# D_Input.net
KiCad netlist of a schematic drawn in Altium Designer
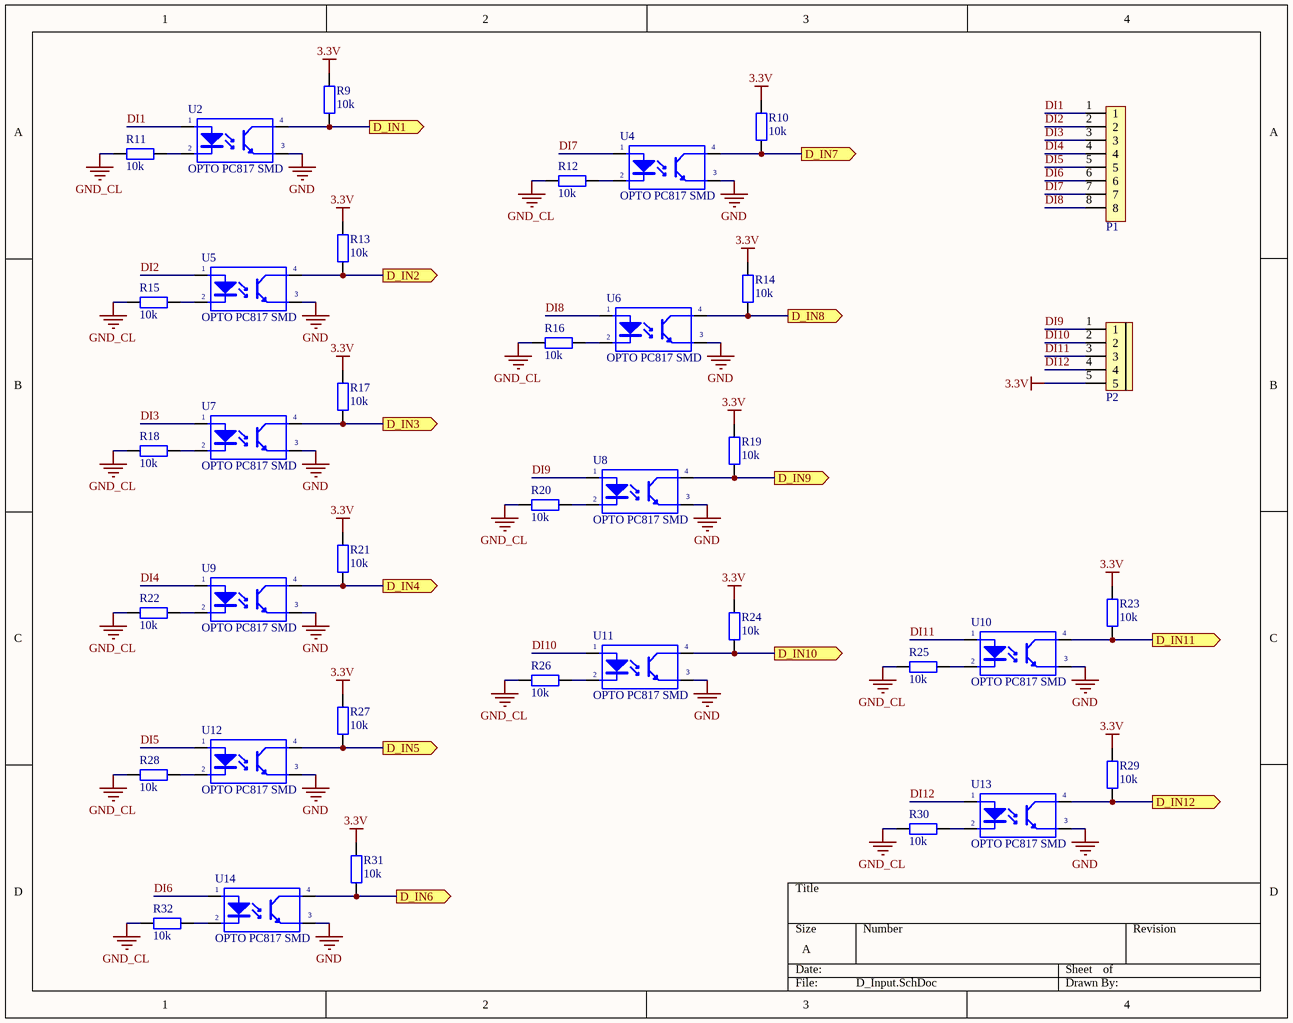
[diagram p0: D_Input.SchDoc]

(export (version "E")
  (design (tool "Eeschema 10.0.6"))
  (components
    (comp (ref "P1")
      (value "CON 8 EDG5.08")
      (footprint "CON 8 8EDG5.08")
      (description "Cắm")
      (libsource (lib "Altium_Lib_by_KhueNguyenCreator") (part "CON 8 EDG5.08"))
    )
    (comp (ref "P2")
      (value "CON 5 EDG5.08")
      (footprint "CON 5 5EDG5.08")
      (description "Cắm")
      (libsource (lib "Altium_Lib_by_KhueNguyenCreator") (part "CON 5 EDG5.08"))
    )
    (comp (ref "R9")
      (value "10k")
      (footprint "tro smd 0805")
      (description "Dán")
      (libsource (lib "Altium_Lib_by_KhueNguyenCreator") (part "Tro 0805 1% 10k"))
    )
    (comp (ref "R10")
      (value "10k")
      (footprint "tro smd 0805")
      (description "Dán")
      (libsource (lib "Altium_Lib_by_KhueNguyenCreator") (part "Tro 0805 1% 10k"))
    )
    (comp (ref "R11")
      (value "10k")
      (footprint "tro smd 0805")
      (description "Dán")
      (libsource (lib "Altium_Lib_by_KhueNguyenCreator") (part "Tro 0805 1% 10k"))
    )
    (comp (ref "R12")
      (value "10k")
      (footprint "tro smd 0805")
      (description "Dán")
      (libsource (lib "Altium_Lib_by_KhueNguyenCreator") (part "Tro 0805 1% 10k"))
    )
    (comp (ref "R13")
      (value "10k")
      (footprint "tro smd 0805")
      (description "Dán")
      (libsource (lib "Altium_Lib_by_KhueNguyenCreator") (part "Tro 0805 1% 10k"))
    )
    (comp (ref "R14")
      (value "10k")
      (footprint "tro smd 0805")
      (description "Dán")
      (libsource (lib "Altium_Lib_by_KhueNguyenCreator") (part "Tro 0805 1% 10k"))
    )
    (comp (ref "R15")
      (value "10k")
      (footprint "tro smd 0805")
      (description "Dán")
      (libsource (lib "Altium_Lib_by_KhueNguyenCreator") (part "Tro 0805 1% 10k"))
    )
    (comp (ref "R16")
      (value "10k")
      (footprint "tro smd 0805")
      (description "Dán")
      (libsource (lib "Altium_Lib_by_KhueNguyenCreator") (part "Tro 0805 1% 10k"))
    )
    (comp (ref "R17")
      (value "10k")
      (footprint "tro smd 0805")
      (description "Dán")
      (libsource (lib "Altium_Lib_by_KhueNguyenCreator") (part "Tro 0805 1% 10k"))
    )
    (comp (ref "R18")
      (value "10k")
      (footprint "tro smd 0805")
      (description "Dán")
      (libsource (lib "Altium_Lib_by_KhueNguyenCreator") (part "Tro 0805 1% 10k"))
    )
    (comp (ref "R19")
      (value "10k")
      (footprint "tro smd 0805")
      (description "Dán")
      (libsource (lib "Altium_Lib_by_KhueNguyenCreator") (part "Tro 0805 1% 10k"))
    )
    (comp (ref "R20")
      (value "10k")
      (footprint "tro smd 0805")
      (description "Dán")
      (libsource (lib "Altium_Lib_by_KhueNguyenCreator") (part "Tro 0805 1% 10k"))
    )
    (comp (ref "R21")
      (value "10k")
      (footprint "tro smd 0805")
      (description "Dán")
      (libsource (lib "Altium_Lib_by_KhueNguyenCreator") (part "Tro 0805 1% 10k"))
    )
    (comp (ref "R22")
      (value "10k")
      (footprint "tro smd 0805")
      (description "Dán")
      (libsource (lib "Altium_Lib_by_KhueNguyenCreator") (part "Tro 0805 1% 10k"))
    )
    (comp (ref "R23")
      (value "10k")
      (footprint "tro smd 0805")
      (description "Dán")
      (libsource (lib "Altium_Lib_by_KhueNguyenCreator") (part "Tro 0805 1% 10k"))
    )
    (comp (ref "R24")
      (value "10k")
      (footprint "tro smd 0805")
      (description "Dán")
      (libsource (lib "Altium_Lib_by_KhueNguyenCreator") (part "Tro 0805 1% 10k"))
    )
    (comp (ref "R25")
      (value "10k")
      (footprint "tro smd 0805")
      (description "Dán")
      (libsource (lib "Altium_Lib_by_KhueNguyenCreator") (part "Tro 0805 1% 10k"))
    )
    (comp (ref "R26")
      (value "10k")
      (footprint "tro smd 0805")
      (description "Dán")
      (libsource (lib "Altium_Lib_by_KhueNguyenCreator") (part "Tro 0805 1% 10k"))
    )
    (comp (ref "R27")
      (value "10k")
      (footprint "tro smd 0805")
      (description "Dán")
      (libsource (lib "Altium_Lib_by_KhueNguyenCreator") (part "Tro 0805 1% 10k"))
    )
    (comp (ref "R28")
      (value "10k")
      (footprint "tro smd 0805")
      (description "Dán")
      (libsource (lib "Altium_Lib_by_KhueNguyenCreator") (part "Tro 0805 1% 10k"))
    )
    (comp (ref "R29")
      (value "10k")
      (footprint "tro smd 0805")
      (description "Dán")
      (libsource (lib "Altium_Lib_by_KhueNguyenCreator") (part "Tro 0805 1% 10k"))
    )
    (comp (ref "R30")
      (value "10k")
      (footprint "tro smd 0805")
      (description "Dán")
      (libsource (lib "Altium_Lib_by_KhueNguyenCreator") (part "Tro 0805 1% 10k"))
    )
    (comp (ref "R31")
      (value "10k")
      (footprint "tro smd 0805")
      (description "Dán")
      (libsource (lib "Altium_Lib_by_KhueNguyenCreator") (part "Tro 0805 1% 10k"))
    )
    (comp (ref "R32")
      (value "10k")
      (footprint "tro smd 0805")
      (description "Dán")
      (libsource (lib "Altium_Lib_by_KhueNguyenCreator") (part "Tro 0805 1% 10k"))
    )
    (comp (ref "U2")
      (value "OPTO PC817 SMD")
      (footprint "SOP4")
      (description "Single Opto")
      (libsource (lib "Altium_Lib_by_KhueNguyenCreator") (part "OPTO PC817 SMD"))
    )
    (comp (ref "U4")
      (value "OPTO PC817 SMD")
      (footprint "SOP4")
      (description "Single Opto")
      (libsource (lib "Altium_Lib_by_KhueNguyenCreator") (part "OPTO PC817 SMD"))
    )
    (comp (ref "U5")
      (value "OPTO PC817 SMD")
      (footprint "SOP4")
      (description "Single Opto")
      (libsource (lib "Altium_Lib_by_KhueNguyenCreator") (part "OPTO PC817 SMD"))
    )
    (comp (ref "U6")
      (value "OPTO PC817 SMD")
      (footprint "SOP4")
      (description "Single Opto")
      (libsource (lib "Altium_Lib_by_KhueNguyenCreator") (part "OPTO PC817 SMD"))
    )
    (comp (ref "U7")
      (value "OPTO PC817 SMD")
      (footprint "SOP4")
      (description "Single Opto")
      (libsource (lib "Altium_Lib_by_KhueNguyenCreator") (part "OPTO PC817 SMD"))
    )
    (comp (ref "U8")
      (value "OPTO PC817 SMD")
      (footprint "SOP4")
      (description "Single Opto")
      (libsource (lib "Altium_Lib_by_KhueNguyenCreator") (part "OPTO PC817 SMD"))
    )
    (comp (ref "U9")
      (value "OPTO PC817 SMD")
      (footprint "SOP4")
      (description "Single Opto")
      (libsource (lib "Altium_Lib_by_KhueNguyenCreator") (part "OPTO PC817 SMD"))
    )
    (comp (ref "U10")
      (value "OPTO PC817 SMD")
      (footprint "SOP4")
      (description "Single Opto")
      (libsource (lib "Altium_Lib_by_KhueNguyenCreator") (part "OPTO PC817 SMD"))
    )
    (comp (ref "U11")
      (value "OPTO PC817 SMD")
      (footprint "SOP4")
      (description "Single Opto")
      (libsource (lib "Altium_Lib_by_KhueNguyenCreator") (part "OPTO PC817 SMD"))
    )
    (comp (ref "U12")
      (value "OPTO PC817 SMD")
      (footprint "SOP4")
      (description "Single Opto")
      (libsource (lib "Altium_Lib_by_KhueNguyenCreator") (part "OPTO PC817 SMD"))
    )
    (comp (ref "U13")
      (value "OPTO PC817 SMD")
      (footprint "SOP4")
      (description "Single Opto")
      (libsource (lib "Altium_Lib_by_KhueNguyenCreator") (part "OPTO PC817 SMD"))
    )
    (comp (ref "U14")
      (value "OPTO PC817 SMD")
      (footprint "SOP4")
      (description "Single Opto")
      (libsource (lib "Altium_Lib_by_KhueNguyenCreator") (part "OPTO PC817 SMD"))
    )
  )
  (nets
    (net (code "1") (name "/DI1") (class "Default")
      (node (ref "P1") (pin "1") (pinfunction "1_1") (pintype "passive"))
      (node (ref "U2") (pin "1") (pinfunction "A_1") (pintype "passive"))
    )
    (net (code "2") (name "/DI2") (class "Default")
      (node (ref "P1") (pin "2") (pinfunction "2_2") (pintype "passive"))
      (node (ref "U5") (pin "1") (pinfunction "A_1") (pintype "passive"))
    )
    (net (code "3") (name "/DI3") (class "Default")
      (node (ref "P1") (pin "3") (pinfunction "3_3") (pintype "passive"))
      (node (ref "U7") (pin "1") (pinfunction "A_1") (pintype "passive"))
    )
    (net (code "4") (name "/DI4") (class "Default")
      (node (ref "P1") (pin "4") (pinfunction "4_4") (pintype "passive"))
      (node (ref "U9") (pin "1") (pinfunction "A_1") (pintype "passive"))
    )
    (net (code "5") (name "/DI5") (class "Default")
      (node (ref "P1") (pin "5") (pinfunction "5_5") (pintype "passive"))
      (node (ref "U12") (pin "1") (pinfunction "A_1") (pintype "passive"))
    )
    (net (code "6") (name "/DI6") (class "Default")
      (node (ref "P1") (pin "6") (pinfunction "6_6") (pintype "passive"))
      (node (ref "U14") (pin "1") (pinfunction "A_1") (pintype "passive"))
    )
    (net (code "7") (name "/DI7") (class "Default")
      (node (ref "P1") (pin "7") (pinfunction "7_7") (pintype "passive"))
      (node (ref "U4") (pin "1") (pinfunction "A_1") (pintype "passive"))
    )
    (net (code "8") (name "/DI8") (class "Default")
      (node (ref "P1") (pin "8") (pinfunction "8_8") (pintype "passive"))
      (node (ref "U6") (pin "1") (pinfunction "A_1") (pintype "passive"))
    )
    (net (code "9") (name "/DI9") (class "Default")
      (node (ref "P2") (pin "1") (pinfunction "1_1") (pintype "passive"))
      (node (ref "U8") (pin "1") (pinfunction "A_1") (pintype "passive"))
    )
    (net (code "10") (name "/DI10") (class "Default")
      (node (ref "P2") (pin "2") (pinfunction "2_2") (pintype "passive"))
      (node (ref "U11") (pin "1") (pinfunction "A_1") (pintype "passive"))
    )
    (net (code "11") (name "/DI11") (class "Default")
      (node (ref "P2") (pin "3") (pinfunction "3_3") (pintype "passive"))
      (node (ref "U10") (pin "1") (pinfunction "A_1") (pintype "passive"))
    )
    (net (code "12") (name "/DI12") (class "Default")
      (node (ref "P2") (pin "4") (pinfunction "4_4") (pintype "passive"))
      (node (ref "U13") (pin "1") (pinfunction "A_1") (pintype "passive"))
    )
    (net (code "13") (name "/D_IN1") (class "Default")
      (node (ref "R9") (pin "1") (pinfunction "1_1") (pintype "passive"))
      (node (ref "U2") (pin "4") (pinfunction "C_4") (pintype "passive"))
    )
    (net (code "14") (name "/D_IN2") (class "Default")
      (node (ref "R13") (pin "1") (pinfunction "1_1") (pintype "passive"))
      (node (ref "U5") (pin "4") (pinfunction "C_4") (pintype "passive"))
    )
    (net (code "15") (name "/D_IN3") (class "Default")
      (node (ref "R17") (pin "1") (pinfunction "1_1") (pintype "passive"))
      (node (ref "U7") (pin "4") (pinfunction "C_4") (pintype "passive"))
    )
    (net (code "16") (name "/D_IN4") (class "Default")
      (node (ref "R21") (pin "1") (pinfunction "1_1") (pintype "passive"))
      (node (ref "U9") (pin "4") (pinfunction "C_4") (pintype "passive"))
    )
    (net (code "17") (name "/D_IN5") (class "Default")
      (node (ref "R27") (pin "1") (pinfunction "1_1") (pintype "passive"))
      (node (ref "U12") (pin "4") (pinfunction "C_4") (pintype "passive"))
    )
    (net (code "18") (name "/D_IN6") (class "Default")
      (node (ref "R31") (pin "1") (pinfunction "1_1") (pintype "passive"))
      (node (ref "U14") (pin "4") (pinfunction "C_4") (pintype "passive"))
    )
    (net (code "19") (name "/D_IN7") (class "Default")
      (node (ref "R10") (pin "1") (pinfunction "1_1") (pintype "passive"))
      (node (ref "U4") (pin "4") (pinfunction "C_4") (pintype "passive"))
    )
    (net (code "20") (name "/D_IN8") (class "Default")
      (node (ref "R14") (pin "1") (pinfunction "1_1") (pintype "passive"))
      (node (ref "U6") (pin "4") (pinfunction "C_4") (pintype "passive"))
    )
    (net (code "21") (name "/D_IN9") (class "Default")
      (node (ref "R19") (pin "1") (pinfunction "1_1") (pintype "passive"))
      (node (ref "U8") (pin "4") (pinfunction "C_4") (pintype "passive"))
    )
    (net (code "22") (name "/D_IN10") (class "Default")
      (node (ref "R24") (pin "1") (pinfunction "1_1") (pintype "passive"))
      (node (ref "U11") (pin "4") (pinfunction "C_4") (pintype "passive"))
    )
    (net (code "23") (name "/D_IN11") (class "Default")
      (node (ref "R23") (pin "1") (pinfunction "1_1") (pintype "passive"))
      (node (ref "U10") (pin "4") (pinfunction "C_4") (pintype "passive"))
    )
    (net (code "24") (name "/D_IN12") (class "Default")
      (node (ref "R29") (pin "1") (pinfunction "1_1") (pintype "passive"))
      (node (ref "U13") (pin "4") (pinfunction "C_4") (pintype "passive"))
    )
    (net (code "25") (name "3.3V") (class "Default")
      (node (ref "P2") (pin "5") (pinfunction "5_5") (pintype "passive"))
      (node (ref "R10") (pin "2") (pinfunction "2_2") (pintype "passive"))
      (node (ref "R13") (pin "2") (pinfunction "2_2") (pintype "passive"))
      (node (ref "R14") (pin "2") (pinfunction "2_2") (pintype "passive"))
      (node (ref "R17") (pin "2") (pinfunction "2_2") (pintype "passive"))
      (node (ref "R19") (pin "2") (pinfunction "2_2") (pintype "passive"))
      (node (ref "R21") (pin "2") (pinfunction "2_2") (pintype "passive"))
      (node (ref "R23") (pin "2") (pinfunction "2_2") (pintype "passive"))
      (node (ref "R24") (pin "2") (pinfunction "2_2") (pintype "passive"))
      (node (ref "R27") (pin "2") (pinfunction "2_2") (pintype "passive"))
      (node (ref "R29") (pin "2") (pinfunction "2_2") (pintype "passive"))
      (node (ref "R31") (pin "2") (pinfunction "2_2") (pintype "passive"))
      (node (ref "R9") (pin "2") (pinfunction "2_2") (pintype "passive"))
    )
    (net (code "26") (name "GND") (class "Default")
      (node (ref "U10") (pin "3") (pinfunction "E_3") (pintype "passive"))
      (node (ref "U11") (pin "3") (pinfunction "E_3") (pintype "passive"))
      (node (ref "U12") (pin "3") (pinfunction "E_3") (pintype "passive"))
      (node (ref "U13") (pin "3") (pinfunction "E_3") (pintype "passive"))
      (node (ref "U14") (pin "3") (pinfunction "E_3") (pintype "passive"))
      (node (ref "U2") (pin "3") (pinfunction "E_3") (pintype "passive"))
      (node (ref "U4") (pin "3") (pinfunction "E_3") (pintype "passive"))
      (node (ref "U5") (pin "3") (pinfunction "E_3") (pintype "passive"))
      (node (ref "U6") (pin "3") (pinfunction "E_3") (pintype "passive"))
      (node (ref "U7") (pin "3") (pinfunction "E_3") (pintype "passive"))
      (node (ref "U8") (pin "3") (pinfunction "E_3") (pintype "passive"))
      (node (ref "U9") (pin "3") (pinfunction "E_3") (pintype "passive"))
    )
    (net (code "27") (name "GND_CL") (class "Default")
      (node (ref "R11") (pin "1") (pinfunction "1_1") (pintype "passive"))
      (node (ref "R12") (pin "1") (pinfunction "1_1") (pintype "passive"))
      (node (ref "R15") (pin "1") (pinfunction "1_1") (pintype "passive"))
      (node (ref "R16") (pin "1") (pinfunction "1_1") (pintype "passive"))
      (node (ref "R18") (pin "1") (pinfunction "1_1") (pintype "passive"))
      (node (ref "R20") (pin "1") (pinfunction "1_1") (pintype "passive"))
      (node (ref "R22") (pin "1") (pinfunction "1_1") (pintype "passive"))
      (node (ref "R25") (pin "1") (pinfunction "1_1") (pintype "passive"))
      (node (ref "R26") (pin "1") (pinfunction "1_1") (pintype "passive"))
      (node (ref "R28") (pin "1") (pinfunction "1_1") (pintype "passive"))
      (node (ref "R30") (pin "1") (pinfunction "1_1") (pintype "passive"))
      (node (ref "R32") (pin "1") (pinfunction "1_1") (pintype "passive"))
    )
    (net (code "28") (name "Net-(U2-K)") (class "Default")
      (node (ref "R11") (pin "2") (pinfunction "2_2") (pintype "passive"))
      (node (ref "U2") (pin "2") (pinfunction "K_2") (pintype "passive"))
    )
    (net (code "29") (name "Net-(U4-K)") (class "Default")
      (node (ref "R12") (pin "2") (pinfunction "2_2") (pintype "passive"))
      (node (ref "U4") (pin "2") (pinfunction "K_2") (pintype "passive"))
    )
    (net (code "30") (name "Net-(U5-K)") (class "Default")
      (node (ref "R15") (pin "2") (pinfunction "2_2") (pintype "passive"))
      (node (ref "U5") (pin "2") (pinfunction "K_2") (pintype "passive"))
    )
    (net (code "31") (name "Net-(U6-K)") (class "Default")
      (node (ref "R16") (pin "2") (pinfunction "2_2") (pintype "passive"))
      (node (ref "U6") (pin "2") (pinfunction "K_2") (pintype "passive"))
    )
    (net (code "32") (name "Net-(U7-K)") (class "Default")
      (node (ref "R18") (pin "2") (pinfunction "2_2") (pintype "passive"))
      (node (ref "U7") (pin "2") (pinfunction "K_2") (pintype "passive"))
    )
    (net (code "33") (name "Net-(U8-K)") (class "Default")
      (node (ref "R20") (pin "2") (pinfunction "2_2") (pintype "passive"))
      (node (ref "U8") (pin "2") (pinfunction "K_2") (pintype "passive"))
    )
    (net (code "34") (name "Net-(U9-K)") (class "Default")
      (node (ref "R22") (pin "2") (pinfunction "2_2") (pintype "passive"))
      (node (ref "U9") (pin "2") (pinfunction "K_2") (pintype "passive"))
    )
    (net (code "35") (name "Net-(U10-K)") (class "Default")
      (node (ref "R25") (pin "2") (pinfunction "2_2") (pintype "passive"))
      (node (ref "U10") (pin "2") (pinfunction "K_2") (pintype "passive"))
    )
    (net (code "36") (name "Net-(U11-K)") (class "Default")
      (node (ref "R26") (pin "2") (pinfunction "2_2") (pintype "passive"))
      (node (ref "U11") (pin "2") (pinfunction "K_2") (pintype "passive"))
    )
    (net (code "37") (name "Net-(U12-K)") (class "Default")
      (node (ref "R28") (pin "2") (pinfunction "2_2") (pintype "passive"))
      (node (ref "U12") (pin "2") (pinfunction "K_2") (pintype "passive"))
    )
    (net (code "38") (name "Net-(U13-K)") (class "Default")
      (node (ref "R30") (pin "2") (pinfunction "2_2") (pintype "passive"))
      (node (ref "U13") (pin "2") (pinfunction "K_2") (pintype "passive"))
    )
    (net (code "39") (name "Net-(U14-K)") (class "Default")
      (node (ref "R32") (pin "2") (pinfunction "2_2") (pintype "passive"))
      (node (ref "U14") (pin "2") (pinfunction "K_2") (pintype "passive"))
    )
  )
)
